# TouchSensor_WGP.net
KiCad netlist of a schematic drawn in EAGLE
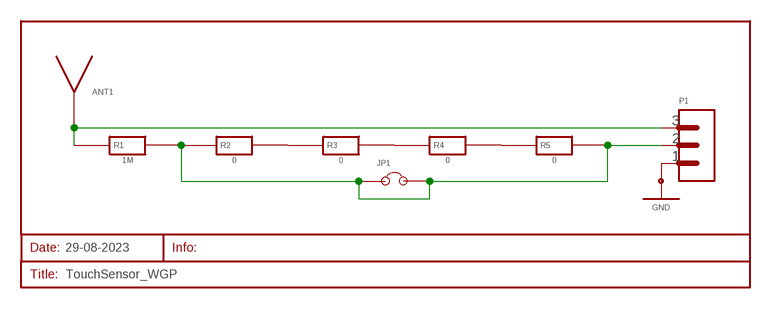
[diagram p0: schematic, sheet 1]

(export (version "E")
  (design (tool "Eeschema 10.0.6"))
  (components
    (comp (ref "JP1")
      (value "JUMPER_2-WAY_PCB_B")
      (footprint "eagle-import:PCB_JUMPER_2-WAY_B")
      (libsource (lib "eagle-import") (part "JUMPER_2-WAY_PCB_B"))
    )
    (comp (ref "P1")
      (value "PORT_3_PIN_HEADER")
      (footprint "eagle-import:HEADER_3_PIN")
      (libsource (lib "eagle-import") (part "PORT_3_PIN_HEADER"))
    )
    (comp (ref "R1")
      (value "1M")
      (footprint "eagle-import:RESISTOR_10.16MM")
      (libsource (lib "eagle-import") (part "RESISTOR"))
    )
    (comp (ref "R2")
      (value "0")
      (footprint "eagle-import:RESISTOR_10.16MM")
      (libsource (lib "eagle-import") (part "RESISTOR"))
    )
    (comp (ref "R3")
      (value "0")
      (footprint "eagle-import:RESISTOR_10.16MM")
      (libsource (lib "eagle-import") (part "RESISTOR"))
    )
    (comp (ref "R4")
      (value "0")
      (footprint "eagle-import:RESISTOR_10.16MM")
      (libsource (lib "eagle-import") (part "RESISTOR"))
    )
    (comp (ref "R5")
      (value "0")
      (footprint "eagle-import:RESISTOR_10.16MM")
      (libsource (lib "eagle-import") (part "RESISTOR"))
    )
    (comp (ref "SCHEMATIC1")
      (value "29-08-2023")
      (footprint "eagle-import:SHEET")
      (libsource (lib "eagle-import") (part "SHEET"))
    )
  )
  (nets
    (net (code "1") (name "ANTENNA") (class "Default")
      (node (ref "P1") (pin "3") (pinfunction "3_3") (pintype "bidirectional"))
      (node (ref "R1") (pin "1") (pinfunction "1_1") (pintype "bidirectional"))
    )
    (net (code "2") (name "GND") (class "Default")
      (node (ref "P1") (pin "1") (pinfunction "1_1") (pintype "bidirectional"))
    )
    (net (code "3") (name "Net-(JP1-Pad1)") (class "Default")
      (node (ref "JP1") (pin "1") (pinfunction "1_1") (pintype "bidirectional"))
      (node (ref "JP1") (pin "2") (pinfunction "2_2") (pintype "bidirectional"))
      (node (ref "P1") (pin "2") (pinfunction "2_2") (pintype "bidirectional"))
      (node (ref "R1") (pin "2") (pinfunction "2_2") (pintype "bidirectional"))
      (node (ref "R2") (pin "1") (pinfunction "1_1") (pintype "bidirectional"))
      (node (ref "R5") (pin "2") (pinfunction "2_2") (pintype "bidirectional"))
    )
    (net (code "4") (name "Net-(R2-Pad2)") (class "Default")
      (node (ref "R2") (pin "2") (pinfunction "2_2") (pintype "bidirectional"))
      (node (ref "R3") (pin "1") (pinfunction "1_1") (pintype "bidirectional"))
    )
    (net (code "5") (name "Net-(R3-Pad2)") (class "Default")
      (node (ref "R3") (pin "2") (pinfunction "2_2") (pintype "bidirectional"))
      (node (ref "R4") (pin "1") (pinfunction "1_1") (pintype "bidirectional"))
    )
    (net (code "6") (name "Net-(R4-Pad2)") (class "Default")
      (node (ref "R4") (pin "2") (pinfunction "2_2") (pintype "bidirectional"))
      (node (ref "R5") (pin "1") (pinfunction "1_1") (pintype "bidirectional"))
    )
  )
)
